# UnipolarMotor.net
KiCad netlist of a schematic drawn in EAGLE
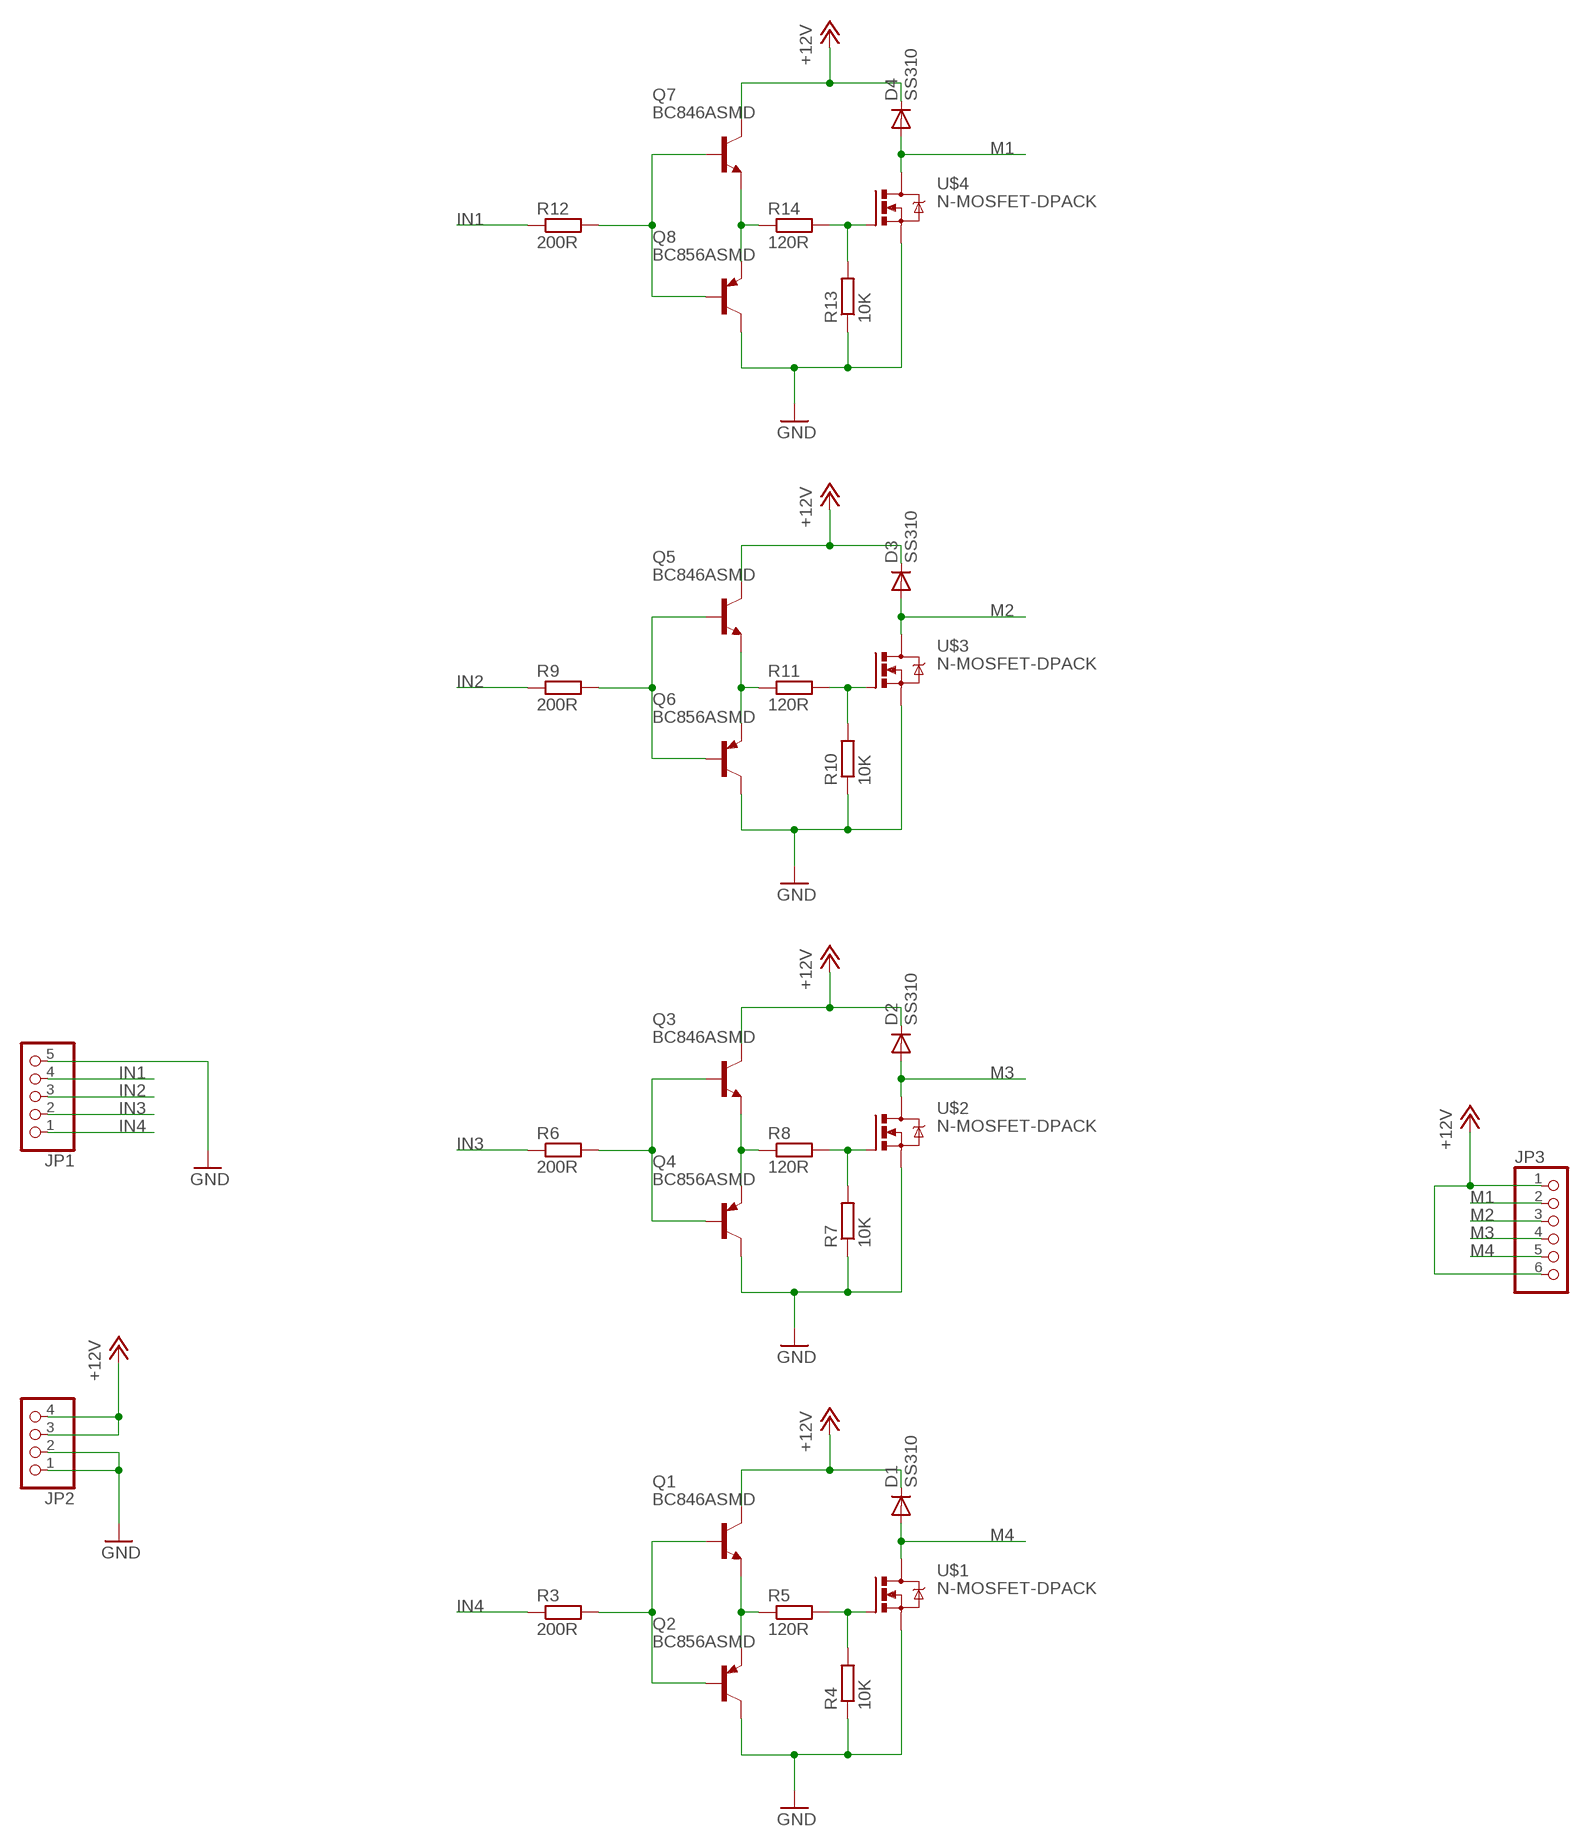
[diagram p0: schematic, sheet 1]

(export (version "E")
  (design (tool "Eeschema 10.0.6"))
  (components
    (comp (ref "D1")
      (value "SS310")
      (footprint "eagle-import:SMA-DIODE_ALT")
      (libsource (lib "eagle-import") (part "DIODESMA-ALT"))
    )
    (comp (ref "D2")
      (value "SS310")
      (footprint "eagle-import:SMA-DIODE_ALT")
      (libsource (lib "eagle-import") (part "DIODESMA-ALT"))
    )
    (comp (ref "D3")
      (value "SS310")
      (footprint "eagle-import:SMA-DIODE_ALT")
      (libsource (lib "eagle-import") (part "DIODESMA-ALT"))
    )
    (comp (ref "D4")
      (value "SS310")
      (footprint "eagle-import:SMA-DIODE_ALT")
      (libsource (lib "eagle-import") (part "DIODESMA-ALT"))
    )
    (comp (ref "JP1")
      (value "PINHD-1X5")
      (footprint "eagle-import:1X05")
      (libsource (lib "eagle-import") (part "PINHD-1X5"))
    )
    (comp (ref "JP2")
      (value "PINHD-1X4")
      (footprint "eagle-import:1X04")
      (libsource (lib "eagle-import") (part "PINHD-1X4"))
    )
    (comp (ref "JP3")
      (value "PINHD-1X6")
      (footprint "eagle-import:1X06")
      (libsource (lib "eagle-import") (part "PINHD-1X6"))
    )
    (comp (ref "Q1")
      (value "BC846ASMD")
      (footprint "eagle-import:SOT23")
      (libsource (lib "eagle-import") (part "BC846SMDA"))
    )
    (comp (ref "Q2")
      (value "BC856ASMD")
      (footprint "eagle-import:SOT23-BEC")
      (libsource (lib "eagle-import") (part "BC856SMDA"))
    )
    (comp (ref "Q3")
      (value "BC846ASMD")
      (footprint "eagle-import:SOT23")
      (libsource (lib "eagle-import") (part "BC846SMDA"))
    )
    (comp (ref "Q4")
      (value "BC856ASMD")
      (footprint "eagle-import:SOT23-BEC")
      (libsource (lib "eagle-import") (part "BC856SMDA"))
    )
    (comp (ref "Q5")
      (value "BC846ASMD")
      (footprint "eagle-import:SOT23")
      (libsource (lib "eagle-import") (part "BC846SMDA"))
    )
    (comp (ref "Q6")
      (value "BC856ASMD")
      (footprint "eagle-import:SOT23-BEC")
      (libsource (lib "eagle-import") (part "BC856SMDA"))
    )
    (comp (ref "Q7")
      (value "BC846ASMD")
      (footprint "eagle-import:SOT23")
      (libsource (lib "eagle-import") (part "BC846SMDA"))
    )
    (comp (ref "Q8")
      (value "BC856ASMD")
      (footprint "eagle-import:SOT23-BEC")
      (libsource (lib "eagle-import") (part "BC856SMDA"))
    )
    (comp (ref "R3")
      (value "200R")
      (footprint "eagle-import:0204_7")
      (libsource (lib "eagle-import") (part "R-EU_0204/7"))
    )
    (comp (ref "R4")
      (value "10K")
      (footprint "eagle-import:R0805")
      (libsource (lib "eagle-import") (part "R-EU_R0805"))
    )
    (comp (ref "R5")
      (value "120R")
      (footprint "eagle-import:R0805")
      (libsource (lib "eagle-import") (part "R-EU_R0805"))
    )
    (comp (ref "R6")
      (value "200R")
      (footprint "eagle-import:0204_7")
      (libsource (lib "eagle-import") (part "R-EU_0204/7"))
    )
    (comp (ref "R7")
      (value "10K")
      (footprint "eagle-import:R0805")
      (libsource (lib "eagle-import") (part "R-EU_R0805"))
    )
    (comp (ref "R8")
      (value "120R")
      (footprint "eagle-import:R0805")
      (libsource (lib "eagle-import") (part "R-EU_R0805"))
    )
    (comp (ref "R9")
      (value "200R")
      (footprint "eagle-import:0204_7")
      (libsource (lib "eagle-import") (part "R-EU_0204/7"))
    )
    (comp (ref "R10")
      (value "10K")
      (footprint "eagle-import:R0805")
      (libsource (lib "eagle-import") (part "R-EU_R0805"))
    )
    (comp (ref "R11")
      (value "120R")
      (footprint "eagle-import:R0805")
      (libsource (lib "eagle-import") (part "R-EU_R0805"))
    )
    (comp (ref "R12")
      (value "200R")
      (footprint "eagle-import:0204_7")
      (libsource (lib "eagle-import") (part "R-EU_0204/7"))
    )
    (comp (ref "R13")
      (value "10K")
      (footprint "eagle-import:R0805")
      (libsource (lib "eagle-import") (part "R-EU_R0805"))
    )
    (comp (ref "R14")
      (value "120R")
      (footprint "eagle-import:R0805")
      (libsource (lib "eagle-import") (part "R-EU_R0805"))
    )
    (comp (ref "U$1")
      (value "N-MOSFET-DPACK")
      (footprint "eagle-import:DPACK")
      (libsource (lib "eagle-import") (part "N-MOSFET-DPACK"))
    )
    (comp (ref "U$2")
      (value "N-MOSFET-DPACK")
      (footprint "eagle-import:DPACK")
      (libsource (lib "eagle-import") (part "N-MOSFET-DPACK"))
    )
    (comp (ref "U$3")
      (value "N-MOSFET-DPACK")
      (footprint "eagle-import:DPACK")
      (libsource (lib "eagle-import") (part "N-MOSFET-DPACK"))
    )
    (comp (ref "U$4")
      (value "N-MOSFET-DPACK")
      (footprint "eagle-import:DPACK")
      (libsource (lib "eagle-import") (part "N-MOSFET-DPACK"))
    )
  )
  (nets
    (net (code "1") (name "+12V") (class "Default")
      (node (ref "D1") (pin "C") (pinfunction "C_C") (pintype "passive"))
      (node (ref "D2") (pin "C") (pinfunction "C_C") (pintype "passive"))
      (node (ref "D3") (pin "C") (pinfunction "C_C") (pintype "passive"))
      (node (ref "D4") (pin "C") (pinfunction "C_C") (pintype "passive"))
      (node (ref "JP2") (pin "3") (pinfunction "3_3") (pintype "passive"))
      (node (ref "JP2") (pin "4") (pinfunction "4_4") (pintype "passive"))
      (node (ref "JP3") (pin "1") (pinfunction "1_1") (pintype "passive"))
      (node (ref "JP3") (pin "6") (pinfunction "6_6") (pintype "passive"))
      (node (ref "Q1") (pin "3") (pinfunction "C_3") (pintype "passive"))
      (node (ref "Q3") (pin "3") (pinfunction "C_3") (pintype "passive"))
      (node (ref "Q5") (pin "3") (pinfunction "C_3") (pintype "passive"))
      (node (ref "Q7") (pin "3") (pinfunction "C_3") (pintype "passive"))
    )
    (net (code "2") (name "/IN1") (class "Default")
      (node (ref "JP1") (pin "4") (pinfunction "4_4") (pintype "passive"))
      (node (ref "R12") (pin "1") (pinfunction "1_1") (pintype "passive"))
    )
    (net (code "3") (name "/IN2") (class "Default")
      (node (ref "JP1") (pin "3") (pinfunction "3_3") (pintype "passive"))
      (node (ref "R9") (pin "1") (pinfunction "1_1") (pintype "passive"))
    )
    (net (code "4") (name "/IN3") (class "Default")
      (node (ref "JP1") (pin "2") (pinfunction "2_2") (pintype "passive"))
      (node (ref "R6") (pin "1") (pinfunction "1_1") (pintype "passive"))
    )
    (net (code "5") (name "/IN4") (class "Default")
      (node (ref "JP1") (pin "1") (pinfunction "1_1") (pintype "passive"))
      (node (ref "R3") (pin "1") (pinfunction "1_1") (pintype "passive"))
    )
    (net (code "6") (name "/M1") (class "Default")
      (node (ref "D4") (pin "A") (pinfunction "A_A") (pintype "passive"))
      (node (ref "JP3") (pin "2") (pinfunction "2_2") (pintype "passive"))
      (node (ref "U$4") (pin "2") (pinfunction "D_2") (pintype "passive"))
    )
    (net (code "7") (name "/M2") (class "Default")
      (node (ref "D3") (pin "A") (pinfunction "A_A") (pintype "passive"))
      (node (ref "JP3") (pin "3") (pinfunction "3_3") (pintype "passive"))
      (node (ref "U$3") (pin "2") (pinfunction "D_2") (pintype "passive"))
    )
    (net (code "8") (name "/M3") (class "Default")
      (node (ref "D2") (pin "A") (pinfunction "A_A") (pintype "passive"))
      (node (ref "JP3") (pin "4") (pinfunction "4_4") (pintype "passive"))
      (node (ref "U$2") (pin "2") (pinfunction "D_2") (pintype "passive"))
    )
    (net (code "9") (name "/M4") (class "Default")
      (node (ref "D1") (pin "A") (pinfunction "A_A") (pintype "passive"))
      (node (ref "JP3") (pin "5") (pinfunction "5_5") (pintype "passive"))
      (node (ref "U$1") (pin "2") (pinfunction "D_2") (pintype "passive"))
    )
    (net (code "10") (name "GND") (class "Default")
      (node (ref "JP1") (pin "5") (pinfunction "5_5") (pintype "passive"))
      (node (ref "JP2") (pin "1") (pinfunction "1_1") (pintype "passive"))
      (node (ref "JP2") (pin "2") (pinfunction "2_2") (pintype "passive"))
      (node (ref "Q2") (pin "C") (pinfunction "C_C") (pintype "passive"))
      (node (ref "Q4") (pin "C") (pinfunction "C_C") (pintype "passive"))
      (node (ref "Q6") (pin "C") (pinfunction "C_C") (pintype "passive"))
      (node (ref "Q8") (pin "C") (pinfunction "C_C") (pintype "passive"))
      (node (ref "R10") (pin "1") (pinfunction "1_1") (pintype "passive"))
      (node (ref "R13") (pin "1") (pinfunction "1_1") (pintype "passive"))
      (node (ref "R4") (pin "1") (pinfunction "1_1") (pintype "passive"))
      (node (ref "R7") (pin "1") (pinfunction "1_1") (pintype "passive"))
      (node (ref "U$1") (pin "3") (pinfunction "S_3") (pintype "passive"))
      (node (ref "U$2") (pin "3") (pinfunction "S_3") (pintype "passive"))
      (node (ref "U$3") (pin "3") (pinfunction "S_3") (pintype "passive"))
      (node (ref "U$4") (pin "3") (pinfunction "S_3") (pintype "passive"))
    )
    (net (code "11") (name "Net-(Q1-B)") (class "Default")
      (node (ref "Q1") (pin "1") (pinfunction "B_1") (pintype "passive"))
      (node (ref "Q2") (pin "B") (pinfunction "B_B") (pintype "passive"))
      (node (ref "R3") (pin "2") (pinfunction "2_2") (pintype "passive"))
    )
    (net (code "12") (name "Net-(Q1-E)") (class "Default")
      (node (ref "Q1") (pin "2") (pinfunction "E_2") (pintype "passive"))
      (node (ref "Q2") (pin "E") (pinfunction "E_E") (pintype "passive"))
      (node (ref "R5") (pin "1") (pinfunction "1_1") (pintype "passive"))
    )
    (net (code "13") (name "Net-(Q3-B)") (class "Default")
      (node (ref "Q3") (pin "1") (pinfunction "B_1") (pintype "passive"))
      (node (ref "Q4") (pin "B") (pinfunction "B_B") (pintype "passive"))
      (node (ref "R6") (pin "2") (pinfunction "2_2") (pintype "passive"))
    )
    (net (code "14") (name "Net-(Q3-E)") (class "Default")
      (node (ref "Q3") (pin "2") (pinfunction "E_2") (pintype "passive"))
      (node (ref "Q4") (pin "E") (pinfunction "E_E") (pintype "passive"))
      (node (ref "R8") (pin "1") (pinfunction "1_1") (pintype "passive"))
    )
    (net (code "15") (name "Net-(Q5-B)") (class "Default")
      (node (ref "Q5") (pin "1") (pinfunction "B_1") (pintype "passive"))
      (node (ref "Q6") (pin "B") (pinfunction "B_B") (pintype "passive"))
      (node (ref "R9") (pin "2") (pinfunction "2_2") (pintype "passive"))
    )
    (net (code "16") (name "Net-(Q5-E)") (class "Default")
      (node (ref "Q5") (pin "2") (pinfunction "E_2") (pintype "passive"))
      (node (ref "Q6") (pin "E") (pinfunction "E_E") (pintype "passive"))
      (node (ref "R11") (pin "1") (pinfunction "1_1") (pintype "passive"))
    )
    (net (code "17") (name "Net-(Q7-B)") (class "Default")
      (node (ref "Q7") (pin "1") (pinfunction "B_1") (pintype "passive"))
      (node (ref "Q8") (pin "B") (pinfunction "B_B") (pintype "passive"))
      (node (ref "R12") (pin "2") (pinfunction "2_2") (pintype "passive"))
    )
    (net (code "18") (name "Net-(Q7-E)") (class "Default")
      (node (ref "Q7") (pin "2") (pinfunction "E_2") (pintype "passive"))
      (node (ref "Q8") (pin "E") (pinfunction "E_E") (pintype "passive"))
      (node (ref "R14") (pin "1") (pinfunction "1_1") (pintype "passive"))
    )
    (net (code "19") (name "Net-(U$1-G)") (class "Default")
      (node (ref "R4") (pin "2") (pinfunction "2_2") (pintype "passive"))
      (node (ref "R5") (pin "2") (pinfunction "2_2") (pintype "passive"))
      (node (ref "U$1") (pin "1") (pinfunction "G_1") (pintype "passive"))
    )
    (net (code "20") (name "Net-(U$2-G)") (class "Default")
      (node (ref "R7") (pin "2") (pinfunction "2_2") (pintype "passive"))
      (node (ref "R8") (pin "2") (pinfunction "2_2") (pintype "passive"))
      (node (ref "U$2") (pin "1") (pinfunction "G_1") (pintype "passive"))
    )
    (net (code "21") (name "Net-(U$3-G)") (class "Default")
      (node (ref "R10") (pin "2") (pinfunction "2_2") (pintype "passive"))
      (node (ref "R11") (pin "2") (pinfunction "2_2") (pintype "passive"))
      (node (ref "U$3") (pin "1") (pinfunction "G_1") (pintype "passive"))
    )
    (net (code "22") (name "Net-(U$4-G)") (class "Default")
      (node (ref "R13") (pin "2") (pinfunction "2_2") (pintype "passive"))
      (node (ref "R14") (pin "2") (pinfunction "2_2") (pintype "passive"))
      (node (ref "U$4") (pin "1") (pinfunction "G_1") (pintype "passive"))
    )
  )
)
